# ECFFL2023-v3-schem.net
KiCad netlist of a schematic drawn in EasyEDA
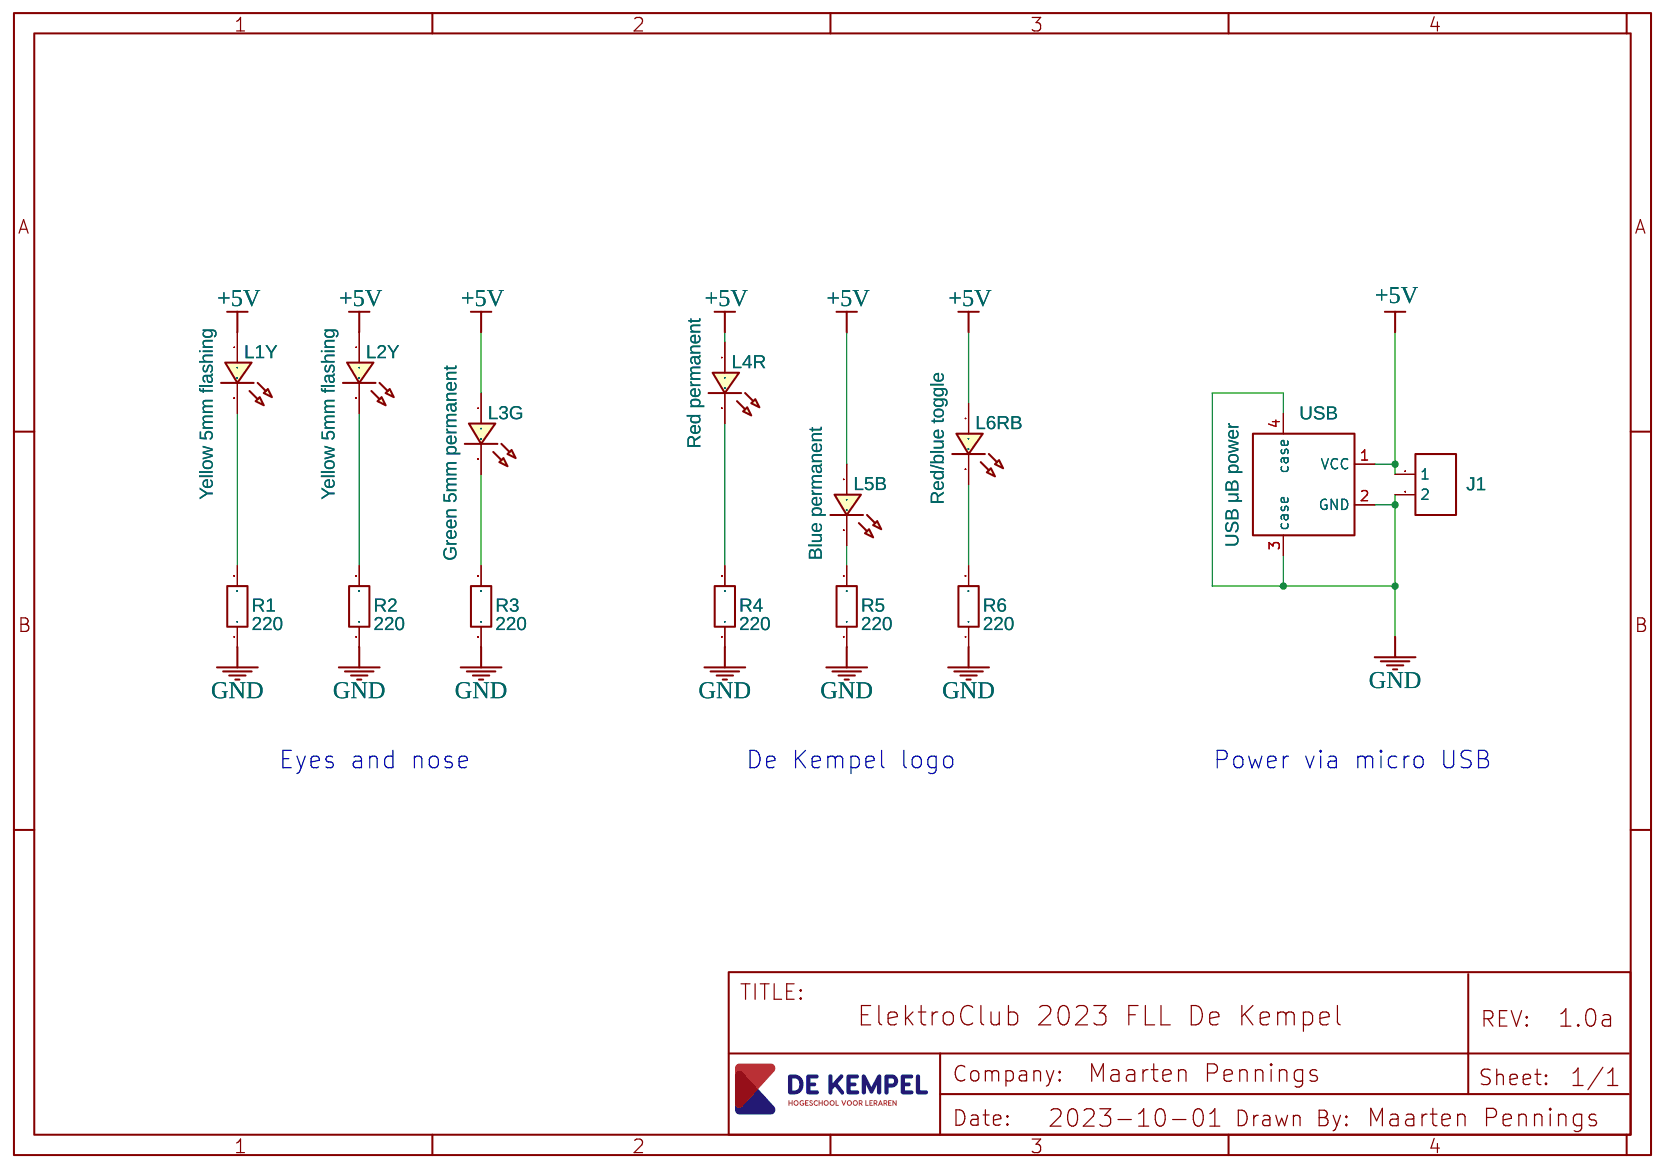
[diagram p0: schematic sheet]

(export (version "E")
  (design (tool "Eeschema 10.0.6"))
  (components
    (comp (ref "J1") (value "HDR-M-2.54_1x2") (libsource (lib "") (part "HDR-M-2.54_1x2")))
    (comp (ref "L1Y")
      (value "Yellow 5mm flashing")
      (fields
        (field (name "Manufacturer Part") "333-2SYGD/S530-E2")
        (field (name "Manufacturer") "EVERLIGHT(台湾亿光)")
      )
      (libsource (lib "") (part "LED-TH-5mm_G_2"))
    )
    (comp (ref "L2Y")
      (value "Yellow 5mm flashing")
      (fields
        (field (name "Manufacturer Part") "333-2SYGD/S530-E2")
        (field (name "Manufacturer") "EVERLIGHT(台湾亿光)")
      )
      (libsource (lib "") (part "LED-TH-5mm_G_1"))
    )
    (comp (ref "L3G")
      (value "Green 5mm permanent")
      (fields
        (field (name "Manufacturer Part") "333-2SYGD/S530-E2")
        (field (name "Manufacturer") "EVERLIGHT(台湾亿光)")
      )
      (libsource (lib "") (part "LED-TH-5mm_G"))
    )
    (comp (ref "L4R")
      (value "Red permanent")
      (fields
        (field (name "Manufacturer Part") "333-2SURD/S530-A3")
        (field (name "Manufacturer") "EVERLIGHT(台湾亿光)")
      )
      (libsource (lib "") (part "LED-TH-5mm_R"))
    )
    (comp (ref "L5B") (value "Blue permanent") (libsource (lib "") (part "LED-TH-5mm_B_1")))
    (comp (ref "L6RB") (value "Red/blue toggle") (libsource (lib "") (part "LED-TH-5mm_B")))
    (comp (ref "R1") (value "220") (libsource (lib "") (part "R_AXIAL-0.4_EU")))
    (comp (ref "R2") (value "220") (libsource (lib "") (part "R_AXIAL-0.4_EU")))
    (comp (ref "R3") (value "220") (libsource (lib "") (part "R_AXIAL-0.4_EU")))
    (comp (ref "R4") (value "220") (libsource (lib "") (part "R_AXIAL-0.4_EU")))
    (comp (ref "R5") (value "220") (libsource (lib "") (part "R_AXIAL-0.4_EU")))
    (comp (ref "R6") (value "220") (libsource (lib "") (part "R_AXIAL-0.4_EU")))
    (comp (ref "USB")
      (value "USB μB power")
      (fields (field (name "Manufacturer Part") "JK1-268") (field (name "Manufacturer") "HBXINTAO"))
      (libsource (lib "") (part "USB μB power"))
    )
  )
  (nets
    (net (code "1") (name "+5V") (class "Default")
      (node (ref "J1") (pin "1") (pinfunction "1_1") (pintype "unspecified"))
      (node (ref "L1Y") (pin "1") (pinfunction "1_1") (pintype "unspecified"))
      (node (ref "L2Y") (pin "1") (pinfunction "1_1") (pintype "unspecified"))
      (node (ref "L3G") (pin "1") (pinfunction "1_1") (pintype "unspecified"))
      (node (ref "L4R") (pin "1") (pinfunction "1_1") (pintype "unspecified"))
      (node (ref "L5B") (pin "1") (pinfunction "1_1") (pintype "unspecified"))
      (node (ref "L6RB") (pin "1") (pinfunction "1_1") (pintype "unspecified"))
      (node (ref "USB") (pin "1") (pinfunction "VCC_1") (pintype "unspecified"))
    )
    (net (code "2") (name "GND") (class "Default")
      (node (ref "J1") (pin "2") (pinfunction "2_2") (pintype "unspecified"))
      (node (ref "R1") (pin "1") (pinfunction "1_1") (pintype "unspecified"))
      (node (ref "R2") (pin "1") (pinfunction "1_1") (pintype "unspecified"))
      (node (ref "R3") (pin "1") (pinfunction "1_1") (pintype "unspecified"))
      (node (ref "R4") (pin "1") (pinfunction "1_1") (pintype "unspecified"))
      (node (ref "R5") (pin "1") (pinfunction "1_1") (pintype "unspecified"))
      (node (ref "R6") (pin "1") (pinfunction "1_1") (pintype "unspecified"))
      (node (ref "USB") (pin "2") (pinfunction "GND_2") (pintype "unspecified"))
      (node (ref "USB") (pin "3") (pinfunction "case_3") (pintype "unspecified"))
      (node (ref "USB") (pin "4") (pinfunction "case_4") (pintype "unspecified"))
    )
    (net (code "3") (name "Net-(L1Y-Pad2)") (class "Default")
      (node (ref "L1Y") (pin "2") (pinfunction "2_2") (pintype "unspecified"))
      (node (ref "R1") (pin "2") (pinfunction "2_2") (pintype "unspecified"))
    )
    (net (code "4") (name "Net-(L2Y-Pad2)") (class "Default")
      (node (ref "L2Y") (pin "2") (pinfunction "2_2") (pintype "unspecified"))
      (node (ref "R2") (pin "2") (pinfunction "2_2") (pintype "unspecified"))
    )
    (net (code "5") (name "Net-(L3G-Pad2)") (class "Default")
      (node (ref "L3G") (pin "2") (pinfunction "2_2") (pintype "unspecified"))
      (node (ref "R3") (pin "2") (pinfunction "2_2") (pintype "unspecified"))
    )
    (net (code "6") (name "Net-(L4R-Pad2)") (class "Default")
      (node (ref "L4R") (pin "2") (pinfunction "2_2") (pintype "unspecified"))
      (node (ref "R4") (pin "2") (pinfunction "2_2") (pintype "unspecified"))
    )
    (net (code "7") (name "Net-(L5B-Pad2)") (class "Default")
      (node (ref "L5B") (pin "2") (pinfunction "2_2") (pintype "unspecified"))
      (node (ref "R5") (pin "2") (pinfunction "2_2") (pintype "unspecified"))
    )
    (net (code "8") (name "Net-(L6RB-Pad2)") (class "Default")
      (node (ref "L6RB") (pin "2") (pinfunction "2_2") (pintype "unspecified"))
      (node (ref "R6") (pin "2") (pinfunction "2_2") (pintype "unspecified"))
    )
  )
)
